# MotorControl.net
KiCad netlist of a schematic drawn in Altium Designer
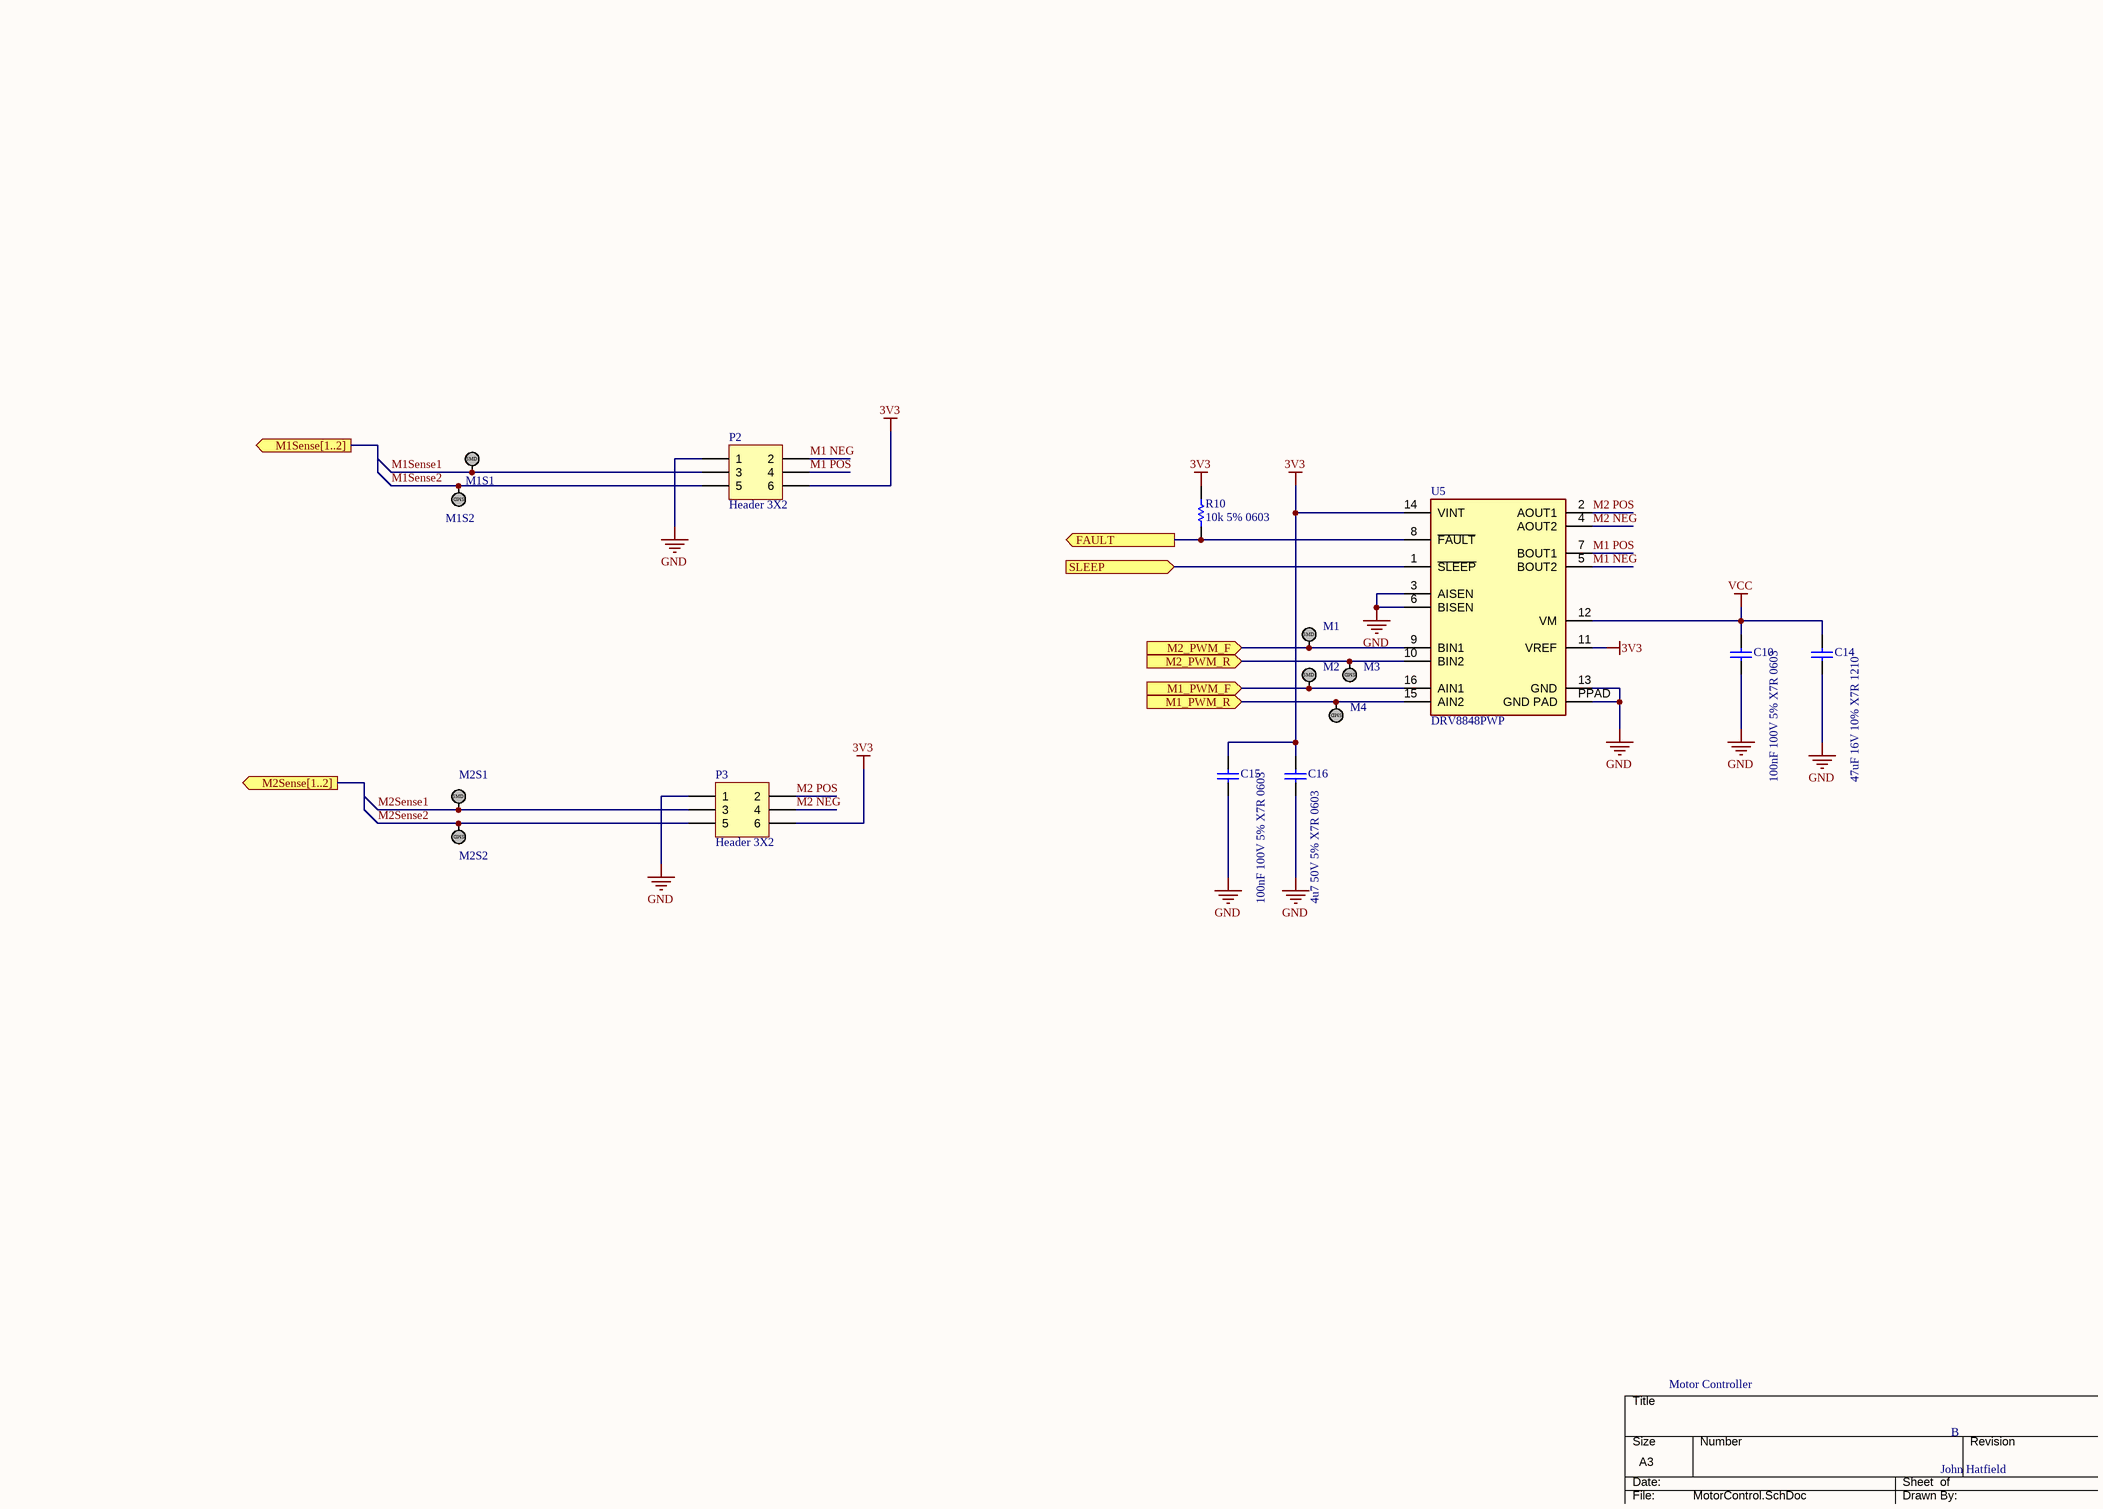
[diagram p0: MotorControl.SchDoc]

(export (version "E")
  (design (tool "Eeschema 10.0.6"))
  (components
    (comp (ref "C10")
      (value "100nF 100V 5% X7R 0603")
      (footprint "Cap_Ceramic_0603")
      (description "Capacitor, Ceramic, SMD, 100nF, 100V, 5%, X7R, 0603")
      (libsource (lib "StandardCapacitors") (part "100nF 100V 5% X7R 0603"))
    )
    (comp (ref "C14")
      (value "47uF 16V 10% X7R 1210")
      (footprint "Cap_Ceramic_1210")
      (description "Capacitor, Ceramic, SMD, 47uF, 16V, 5%, X7R, 1210")
      (libsource (lib "StandardCapacitors") (part "47uF 16V 10% X7R 1210"))
    )
    (comp (ref "C15")
      (value "100nF 100V 5% X7R 0603")
      (footprint "Cap_Ceramic_0603")
      (description "Capacitor, Ceramic, SMD, 100nF, 100V, 5%, X7R, 0603")
      (libsource (lib "StandardCapacitors") (part "100nF 100V 5% X7R 0603"))
    )
    (comp (ref "C16")
      (value "4u7 50V 5% X7R 0603")
      (footprint "Cap_Ceramic_0603")
      (description "Capacitor, Ceramic, SMD, 4u7, 50V, 5%, X7R, 0603")
      (libsource (lib "StandardCapacitors") (part "4u7 50V 5% X7R 0603"))
    )
    (comp (ref "M1")
      (value "TestPoint_SMD")
      (footprint "TestPointSMD")
      (libsource (lib "StandardTest") (part "TestPoint_SMD"))
    )
    (comp (ref "M1S1")
      (value "TestPoint_SMD")
      (footprint "TestPointSMD")
      (libsource (lib "StandardTest") (part "TestPoint_SMD"))
    )
    (comp (ref "M1S2")
      (value "TestPoint_SMD")
      (footprint "TestPointSMD")
      (libsource (lib "StandardTest") (part "TestPoint_SMD"))
    )
    (comp (ref "M2")
      (value "TestPoint_SMD")
      (footprint "TestPointSMD")
      (libsource (lib "StandardTest") (part "TestPoint_SMD"))
    )
    (comp (ref "M2S1")
      (value "TestPoint_SMD")
      (footprint "TestPointSMD")
      (libsource (lib "StandardTest") (part "TestPoint_SMD"))
    )
    (comp (ref "M2S2")
      (value "TestPoint_SMD")
      (footprint "TestPointSMD")
      (libsource (lib "StandardTest") (part "TestPoint_SMD"))
    )
    (comp (ref "M3")
      (value "TestPoint_SMD")
      (footprint "TestPointSMD")
      (libsource (lib "StandardTest") (part "TestPoint_SMD"))
    )
    (comp (ref "M4")
      (value "TestPoint_SMD")
      (footprint "TestPointSMD")
      (libsource (lib "StandardTest") (part "TestPoint_SMD"))
    )
    (comp (ref "P2")
      (value "Header 3X2")
      (footprint "HDR2X3")
      (description "Header, 3-Pin, Dual row")
      (fields (field (name "PUBLISHER") "Altium Limited"))
      (libsource (lib "Miscellaneous Connectors") (part "Header 3X2"))
    )
    (comp (ref "P3")
      (value "Header 3X2")
      (footprint "HDR2X3")
      (description "Header, 3-Pin, Dual row")
      (fields (field (name "PUBLISHER") "Altium Limited"))
      (libsource (lib "Miscellaneous Connectors") (part "Header 3X2"))
    )
    (comp (ref "R10")
      (value "10k 5% 0603")
      (footprint "Res_ThinFilm_0603")
      (description "Resistor, SMD, 10k, 0.1W, 5%, 0603")
      (libsource (lib "StandardResistors") (part "10k 5% 0603"))
    )
    (comp (ref "U5")
      (value "IC_Texas_Instruments_DRV8848PWP_eec")
      (footprint "Texas_Instruments_PWP_R-PDSO-G16_0")
      (description "IC MOTOR DRIVER PAR 16HTSSOP")
      (fields
        (field (name "PART NUMBER") "DRV8848PWP")
        (field (name "VOLTAGE") "18V")
        (field (name "MANUFACTURER") "Texas Instruments")
      )
      (libsource (lib "IC_Texas_Instruments_DRV8848PWP_eec") (part "IC_Texas_Instruments_DRV8848PWP_eec"))
    )
  )
  (nets
    (net (code "1") (name "/FAULT") (class "Default")
      (node (ref "R10") (pin "1") (pinfunction "1_1") (pintype "passive"))
      (node (ref "U5") (pin "8") (pinfunction "~{FAULT}_8") (pintype "passive"))
    )
    (net (code "2") (name "/M1 NEG") (class "Default")
      (node (ref "P2") (pin "2") (pinfunction "2_2") (pintype "passive"))
      (node (ref "U5") (pin "5") (pinfunction "BOUT2_5") (pintype "passive"))
    )
    (net (code "3") (name "/M1 POS") (class "Default")
      (node (ref "P2") (pin "4") (pinfunction "4_4") (pintype "passive"))
      (node (ref "U5") (pin "7") (pinfunction "BOUT1_7") (pintype "passive"))
    )
    (net (code "4") (name "/M1Sense1") (class "Default")
      (node (ref "M1S1") (pin "1") (pinfunction "1_1") (pintype "passive"))
      (node (ref "P2") (pin "3") (pinfunction "3_3") (pintype "passive"))
    )
    (net (code "5") (name "/M1Sense2") (class "Default")
      (node (ref "M1S2") (pin "1") (pinfunction "1_1") (pintype "passive"))
      (node (ref "P2") (pin "5") (pinfunction "5_5") (pintype "passive"))
    )
    (net (code "7") (name "/M1_PWM_F") (class "Default")
      (node (ref "M2") (pin "1") (pinfunction "1_1") (pintype "passive"))
      (node (ref "U5") (pin "16") (pinfunction "AIN1_16") (pintype "passive"))
    )
    (net (code "8") (name "/M1_PWM_R") (class "Default")
      (node (ref "M4") (pin "1") (pinfunction "1_1") (pintype "passive"))
      (node (ref "U5") (pin "15") (pinfunction "AIN2_15") (pintype "passive"))
    )
    (net (code "9") (name "/M2 NEG") (class "Default")
      (node (ref "P3") (pin "4") (pinfunction "4_4") (pintype "passive"))
      (node (ref "U5") (pin "4") (pinfunction "AOUT2_4") (pintype "passive"))
    )
    (net (code "10") (name "/M2 POS") (class "Default")
      (node (ref "P3") (pin "2") (pinfunction "2_2") (pintype "passive"))
      (node (ref "U5") (pin "2") (pinfunction "AOUT1_2") (pintype "passive"))
    )
    (net (code "11") (name "/M2Sense1") (class "Default")
      (node (ref "M2S1") (pin "1") (pinfunction "1_1") (pintype "passive"))
      (node (ref "P3") (pin "3") (pinfunction "3_3") (pintype "passive"))
    )
    (net (code "12") (name "/M2Sense2") (class "Default")
      (node (ref "M2S2") (pin "1") (pinfunction "1_1") (pintype "passive"))
      (node (ref "P3") (pin "5") (pinfunction "5_5") (pintype "passive"))
    )
    (net (code "14") (name "/M2_PWM_F") (class "Default")
      (node (ref "M1") (pin "1") (pinfunction "1_1") (pintype "passive"))
      (node (ref "U5") (pin "9") (pinfunction "BIN1_9") (pintype "passive"))
    )
    (net (code "15") (name "/M2_PWM_R") (class "Default")
      (node (ref "M3") (pin "1") (pinfunction "1_1") (pintype "passive"))
      (node (ref "U5") (pin "10") (pinfunction "BIN2_10") (pintype "passive"))
    )
    (net (code "16") (name "/SLEEP") (class "Default")
      (node (ref "U5") (pin "1") (pinfunction "~{SLEEP}_1") (pintype "passive"))
    )
    (net (code "17") (name "3V3") (class "Default")
      (node (ref "C15") (pin "2") (pinfunction "2_2") (pintype "passive"))
      (node (ref "C16") (pin "2") (pinfunction "2_2") (pintype "passive"))
      (node (ref "P2") (pin "6") (pinfunction "6_6") (pintype "passive"))
      (node (ref "P3") (pin "6") (pinfunction "6_6") (pintype "passive"))
      (node (ref "R10") (pin "2") (pinfunction "2_2") (pintype "passive"))
      (node (ref "U5") (pin "11") (pinfunction "VREF_11") (pintype "passive"))
      (node (ref "U5") (pin "14") (pinfunction "VINT_14") (pintype "passive"))
    )
    (net (code "18") (name "GND") (class "Default")
      (node (ref "C10") (pin "1") (pinfunction "1_1") (pintype "passive"))
      (node (ref "C14") (pin "1") (pinfunction "1_1") (pintype "passive"))
      (node (ref "C15") (pin "1") (pinfunction "1_1") (pintype "passive"))
      (node (ref "C16") (pin "1") (pinfunction "1_1") (pintype "passive"))
      (node (ref "P2") (pin "1") (pinfunction "1_1") (pintype "passive"))
      (node (ref "P3") (pin "1") (pinfunction "1_1") (pintype "passive"))
      (node (ref "U5") (pin "13") (pinfunction "GND_13") (pintype "passive"))
      (node (ref "U5") (pin "3") (pinfunction "AISEN_3") (pintype "passive"))
      (node (ref "U5") (pin "6") (pinfunction "BISEN_6") (pintype "passive"))
      (node (ref "U5") (pin "PPAD") (pinfunction "GND_PAD_PPAD") (pintype "passive"))
    )
    (net (code "19") (name "VCC") (class "Default")
      (node (ref "C10") (pin "2") (pinfunction "2_2") (pintype "passive"))
      (node (ref "C14") (pin "2") (pinfunction "2_2") (pintype "passive"))
      (node (ref "U5") (pin "12") (pinfunction "VM_12") (pintype "passive"))
    )
  )
)
